# Power_Management.net
KiCad netlist of a schematic drawn in Altium Designer
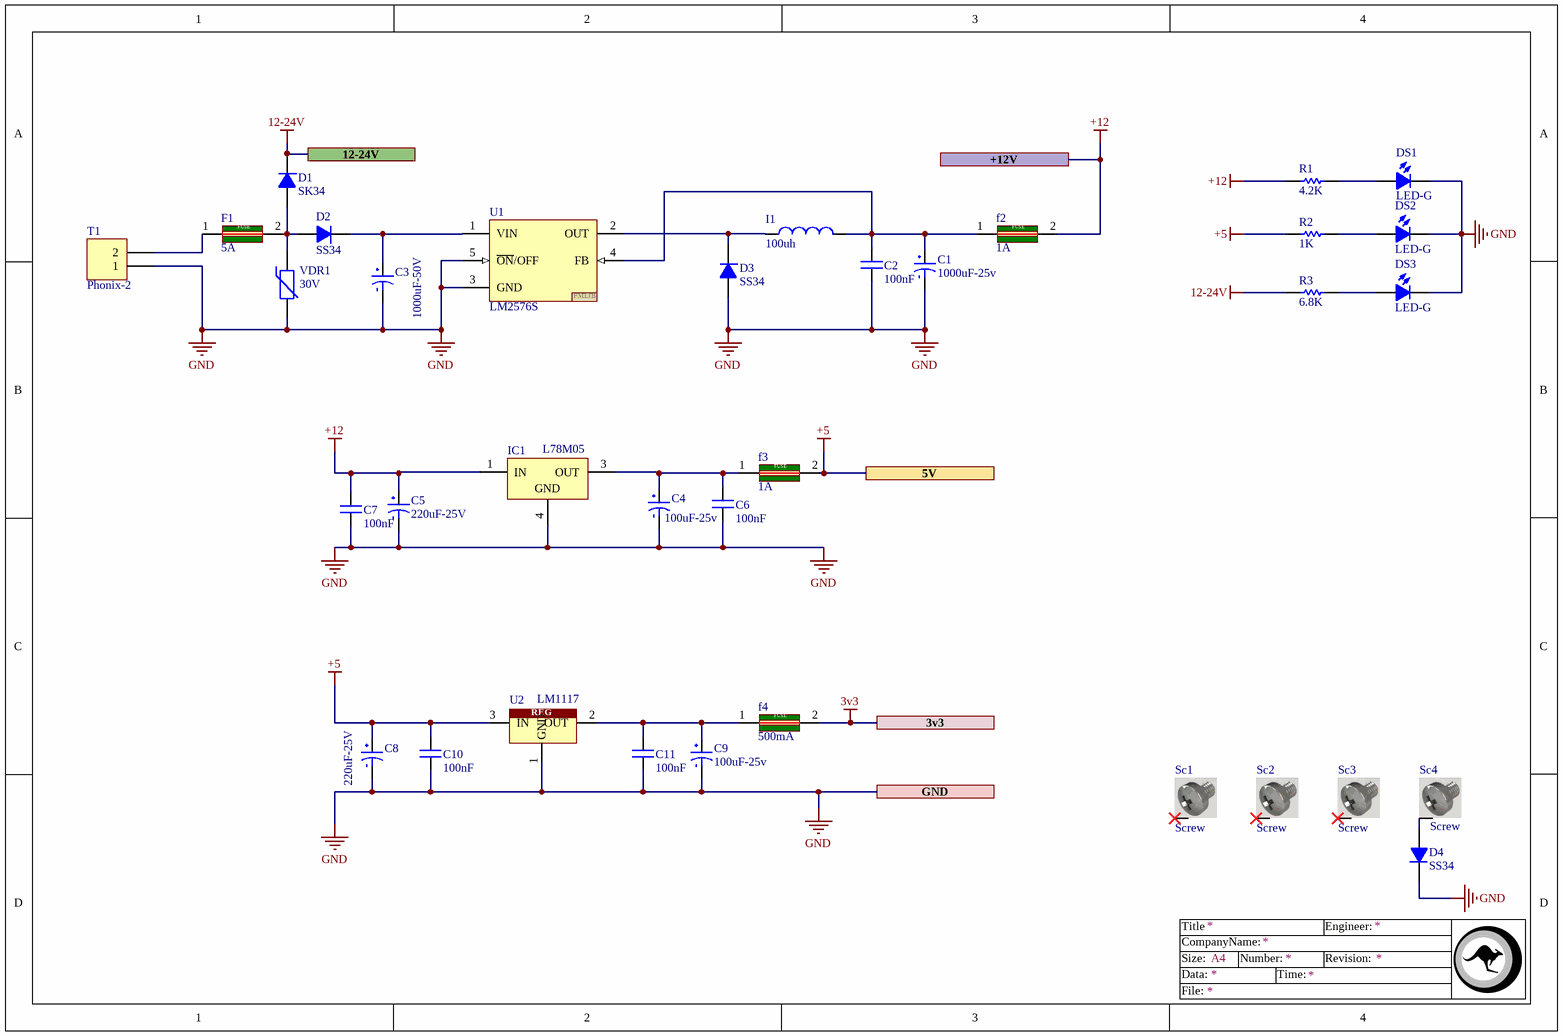
[diagram p0: Power Management.SchDoc]

(export (version "E")
  (design (tool "Eeschema 10.0.6"))
  (components
    (comp (ref "C1")
      (value "1000uF-25v")
      (footprint "Cap_4mm")
      (description "Polarity")
      (libsource (lib "PMLIB2020-V3") (part "Cap_P"))
    )
    (comp (ref "C2")
      (value "100nF")
      (footprint "CAP1206")
      (description "Surface mount Capacitor")
      (libsource (lib "PMLIB2020-V3") (part "Cap"))
    )
    (comp (ref "C3")
      (value "1000uF-50V")
      (footprint "Cap_5mm")
      (description "Polarity")
      (libsource (lib "PMLIB2020-V3") (part "Cap_P"))
    )
    (comp (ref "C4")
      (value "100uF-25v")
      (footprint "Cap_4mm")
      (description "Polarity")
      (libsource (lib "PMLIB2020-V3") (part "Cap_P"))
    )
    (comp (ref "C5")
      (value "220uF-25V")
      (footprint "Cap_4mm")
      (description "Polarity")
      (libsource (lib "PMLIB2020-V3") (part "Cap_P"))
    )
    (comp (ref "C6")
      (value "100nF")
      (footprint "Cap0805")
      (description "Surface mount Capacitor")
      (libsource (lib "PMLIB2020-V3") (part "Cap"))
    )
    (comp (ref "C7")
      (value "100nF")
      (footprint "Cap0805")
      (description "Surface mount Capacitor")
      (libsource (lib "PMLIB2020-V3") (part "Cap"))
    )
    (comp (ref "C8")
      (value "220uF-25V")
      (footprint "CAPMOL_B")
      (description "Polarity")
      (libsource (lib "PMLIB2020-V3") (part "Cap_P"))
    )
    (comp (ref "C9")
      (value "100uF-25v")
      (footprint "CAPMOL_B")
      (description "Polarity")
      (libsource (lib "PMLIB2020-V3") (part "Cap_P"))
    )
    (comp (ref "C10")
      (value "100nF")
      (footprint "Cap0805")
      (description "Surface mount Capacitor")
      (libsource (lib "PMLIB2020-V3") (part "Cap"))
    )
    (comp (ref "C11")
      (value "100nF")
      (footprint "Cap0805")
      (description "Surface mount Capacitor")
      (libsource (lib "PMLIB2020-V3") (part "Cap"))
    )
    (comp (ref "D1")
      (value "SK34")
      (footprint "Diod-3A-SMD")
      (description "Diode")
      (libsource (lib "PMLIB2020-V3") (part "Diode"))
    )
    (comp (ref "D2")
      (value "SS34")
      (footprint "Diod-1A-SMD")
      (description "Diode")
      (libsource (lib "PMLIB2020-V3") (part "Diode"))
    )
    (comp (ref "D3")
      (value "SS34")
      (footprint "Diod-1A-SMD")
      (description "Diode")
      (libsource (lib "PMLIB2020-V3") (part "Diode"))
    )
    (comp (ref "D4")
      (value "SS34")
      (footprint "Diod-1A-SMD")
      (description "Diode")
      (libsource (lib "PMLIB2020-V3") (part "Diode"))
    )
    (comp (ref "DS1")
      (value "LED-G")
      (footprint "Led0805")
      (description "LED")
      (libsource (lib "PMLIB2020-V3") (part "LED"))
    )
    (comp (ref "DS2")
      (value "LED-G")
      (footprint "Led0805")
      (description "LED")
      (libsource (lib "PMLIB2020-V3") (part "LED"))
    )
    (comp (ref "DS3")
      (value "LED-G")
      (footprint "Led0805")
      (description "LED")
      (libsource (lib "PMLIB2020-V3") (part "LED"))
    )
    (comp (ref "F1")
      (value "5A")
      (footprint "Fuse SMD")
      (description "Fuse")
      (libsource (lib "PMLIB2020-V3") (part "Fuse"))
    )
    (comp (ref "f2")
      (value "1A")
      (footprint "1206")
      (description "Fuse")
      (libsource (lib "PMLIB2020-V3") (part "Fuse"))
    )
    (comp (ref "f3")
      (value "1A")
      (footprint "1206")
      (description "Fuse")
      (libsource (lib "PMLIB2020-V3") (part "Fuse"))
    )
    (comp (ref "f4")
      (value "500mA")
      (footprint "1206")
      (description "Fuse")
      (libsource (lib "PMLIB2020-V3") (part "Fuse"))
    )
    (comp (ref "I1")
      (value "100uh")
      (footprint "INDUCTORSquare")
      (description "Indicator")
      (libsource (lib "PMLIB2020-V3") (part "Inductor"))
    )
    (comp (ref "IC1")
      (value "L78M05")
      (footprint "TO-252")
      (description "Precision 500mA Regulator")
      (libsource (lib "PMLIB2020-V3") (part "L78M05"))
    )
    (comp (ref "R1")
      (value "4.2K")
      (footprint "R0805")
      (description "Resistor")
      (libsource (lib "PMLIB2020-V3") (part "Resistor"))
    )
    (comp (ref "R2")
      (value "1K")
      (footprint "R0805")
      (description "Resistor")
      (libsource (lib "PMLIB2020-V3") (part "Resistor"))
    )
    (comp (ref "R3")
      (value "6.8K")
      (footprint "R0805")
      (description "Resistor")
      (libsource (lib "PMLIB2020-V3") (part "Resistor"))
    )
    (comp (ref "Sc1")
      (value "Screw")
      (footprint "Screw")
      (description "Screw 3mm")
      (libsource (lib "PMLIB2020-V3") (part "Screw"))
    )
    (comp (ref "Sc2")
      (value "Screw")
      (footprint "Screw")
      (description "Screw 3mm")
      (libsource (lib "PMLIB2020-V3") (part "Screw"))
    )
    (comp (ref "Sc3")
      (value "Screw")
      (footprint "Screw")
      (description "Screw 3mm")
      (libsource (lib "PMLIB2020-V3") (part "Screw"))
    )
    (comp (ref "Sc4")
      (value "Screw")
      (footprint "Screw")
      (description "Screw 3mm")
      (libsource (lib "PMLIB2020-V3") (part "Screw"))
    )
    (comp (ref "T1")
      (value "Phonix-2")
      (footprint "Phonix-2")
      (description "Connector")
      (libsource (lib "PMLIB2020-V3") (part "Phonix-2"))
    )
    (comp (ref "U1")
      (value "LM2576S")
      (footprint "LM2576S")
      (description "Regulator")
      (libsource (lib "PMLIB2020-V3") (part "LM2576S"))
    )
    (comp (ref "U2")
      (value "LM1117")
      (footprint "DPACK")
      (description "Regulator")
      (libsource (lib "PMLIB2020-V3") (part "LM1117"))
    )
    (comp (ref "VDR1")
      (value "30V")
      (footprint "Varistor")
      (libsource (lib "PMLIB2020-V3") (part "Varistor"))
    )
  )
  (nets
    (net (code "1") (name "+5") (class "Default")
      (node (ref "C10") (pin "2") (pinfunction "2_2") (pintype "passive"))
      (node (ref "C8") (pin "2") (pinfunction "2_2") (pintype "passive"))
      (node (ref "R2") (pin "2") (pinfunction "2_2") (pintype "passive"))
      (node (ref "U2") (pin "3") (pinfunction "IN_3") (pintype "passive"))
      (node (ref "f3") (pin "2") (pinfunction "OUT_2") (pintype "passive"))
    )
    (net (code "2") (name "+12") (class "Default")
      (node (ref "C5") (pin "2") (pinfunction "2_2") (pintype "passive"))
      (node (ref "C7") (pin "2") (pinfunction "2_2") (pintype "passive"))
      (node (ref "IC1") (pin "1") (pinfunction "IN_1") (pintype "power_in"))
      (node (ref "R1") (pin "2") (pinfunction "2_2") (pintype "passive"))
      (node (ref "f2") (pin "2") (pinfunction "OUT_2") (pintype "passive"))
    )
    (net (code "3") (name "3v3") (class "Default")
      (node (ref "f4") (pin "2") (pinfunction "OUT_2") (pintype "passive"))
    )
    (net (code "4") (name "12-24V") (class "Default")
      (node (ref "D1") (pin "K") (pinfunction "K_K") (pintype "passive"))
      (node (ref "R3") (pin "2") (pinfunction "2_2") (pintype "passive"))
    )
    (net (code "5") (name "GND") (class "Default")
      (node (ref "C1") (pin "1") (pinfunction "1_1") (pintype "passive"))
      (node (ref "C10") (pin "1") (pinfunction "1_1") (pintype "passive"))
      (node (ref "C11") (pin "1") (pinfunction "1_1") (pintype "passive"))
      (node (ref "C2") (pin "1") (pinfunction "1_1") (pintype "passive"))
      (node (ref "C3") (pin "1") (pinfunction "1_1") (pintype "passive"))
      (node (ref "C4") (pin "1") (pinfunction "1_1") (pintype "passive"))
      (node (ref "C5") (pin "1") (pinfunction "1_1") (pintype "passive"))
      (node (ref "C6") (pin "1") (pinfunction "1_1") (pintype "passive"))
      (node (ref "C7") (pin "1") (pinfunction "1_1") (pintype "passive"))
      (node (ref "C8") (pin "1") (pinfunction "1_1") (pintype "passive"))
      (node (ref "C9") (pin "1") (pinfunction "1_1") (pintype "passive"))
      (node (ref "D3") (pin "A") (pinfunction "A_A") (pintype "passive"))
      (node (ref "D4") (pin "K") (pinfunction "K_K") (pintype "passive"))
      (node (ref "DS1") (pin "K") (pinfunction "K_K") (pintype "passive"))
      (node (ref "DS2") (pin "K") (pinfunction "K_K") (pintype "passive"))
      (node (ref "DS3") (pin "K") (pinfunction "K_K") (pintype "passive"))
      (node (ref "IC1") (pin "4") (pinfunction "GND_4") (pintype "power_in"))
      (node (ref "T1") (pin "1") (pinfunction "1_1") (pintype "passive"))
      (node (ref "U1") (pin "3") (pinfunction "GND_3") (pintype "power_in"))
      (node (ref "U1") (pin "5") (pinfunction "~{ON}/OFF_5") (pintype "input"))
      (node (ref "U2") (pin "1") (pinfunction "GND_1") (pintype "passive"))
      (node (ref "VDR1") (pin "1") (pinfunction "1_1") (pintype "passive"))
    )
    (net (code "6") (name "Net-(D4-PadA)") (class "Default")
      (node (ref "D4") (pin "A") (pinfunction "A_A") (pintype "passive"))
      (node (ref "Sc4") (pin "S") (pinfunction "S_S") (pintype "passive"))
    )
    (net (code "7") (name "Net-(DS1-PadA)") (class "Default")
      (node (ref "DS1") (pin "A") (pinfunction "A_A") (pintype "passive"))
      (node (ref "R1") (pin "1") (pinfunction "1_1") (pintype "passive"))
    )
    (net (code "8") (name "Net-(DS2-PadA)") (class "Default")
      (node (ref "DS2") (pin "A") (pinfunction "A_A") (pintype "passive"))
      (node (ref "R2") (pin "1") (pinfunction "1_1") (pintype "passive"))
    )
    (net (code "9") (name "Net-(DS3-PadA)") (class "Default")
      (node (ref "DS3") (pin "A") (pinfunction "A_A") (pintype "passive"))
      (node (ref "R3") (pin "1") (pinfunction "1_1") (pintype "passive"))
    )
    (net (code "10") (name "Net-(F1-IN)") (class "Default")
      (node (ref "F1") (pin "1") (pinfunction "IN_1") (pintype "passive"))
      (node (ref "T1") (pin "2") (pinfunction "2_2") (pintype "passive"))
    )
    (net (code "11") (name "Net-(F1-OUT)") (class "Default")
      (node (ref "D1") (pin "A") (pinfunction "A_A") (pintype "passive"))
      (node (ref "D2") (pin "A") (pinfunction "A_A") (pintype "passive"))
      (node (ref "F1") (pin "2") (pinfunction "OUT_2") (pintype "passive"))
      (node (ref "VDR1") (pin "2") (pinfunction "2_2") (pintype "passive"))
    )
    (net (code "12") (name "Net-(IC1-OUT)") (class "Default")
      (node (ref "C4") (pin "2") (pinfunction "2_2") (pintype "passive"))
      (node (ref "C6") (pin "2") (pinfunction "2_2") (pintype "passive"))
      (node (ref "IC1") (pin "3") (pinfunction "OUT_3") (pintype "power_in"))
      (node (ref "f3") (pin "1") (pinfunction "IN_1") (pintype "passive"))
    )
    (net (code "13") (name "Net-(U1-FB)") (class "Default")
      (node (ref "C1") (pin "2") (pinfunction "2_2") (pintype "passive"))
      (node (ref "C2") (pin "2") (pinfunction "2_2") (pintype "passive"))
      (node (ref "I1") (pin "2") (pinfunction "2_2") (pintype "passive"))
      (node (ref "U1") (pin "4") (pinfunction "FB_4") (pintype "input"))
      (node (ref "f2") (pin "1") (pinfunction "IN_1") (pintype "passive"))
    )
    (net (code "14") (name "Net-(U1-OUT)") (class "Default")
      (node (ref "D3") (pin "K") (pinfunction "K_K") (pintype "passive"))
      (node (ref "I1") (pin "1") (pinfunction "1_1") (pintype "passive"))
      (node (ref "U1") (pin "2") (pinfunction "OUT_2") (pintype "power_in"))
    )
    (net (code "15") (name "Net-(U1-VIN)") (class "Default")
      (node (ref "C3") (pin "2") (pinfunction "2_2") (pintype "passive"))
      (node (ref "D2") (pin "K") (pinfunction "K_K") (pintype "passive"))
      (node (ref "U1") (pin "1") (pinfunction "VIN_1") (pintype "power_in"))
    )
    (net (code "16") (name "Net-(U2-OUT)") (class "Default")
      (node (ref "C11") (pin "2") (pinfunction "2_2") (pintype "passive"))
      (node (ref "C9") (pin "2") (pinfunction "2_2") (pintype "passive"))
      (node (ref "U2") (pin "2") (pinfunction "OUT_2") (pintype "passive"))
      (node (ref "f4") (pin "1") (pinfunction "IN_1") (pintype "passive"))
    )
    (net (code "17") (name "unconnected-(Sc1-PadS)") (class "Default")
      (node (ref "Sc1") (pin "S") (pinfunction "S_S") (pintype "passive+no_connect"))
    )
    (net (code "18") (name "unconnected-(Sc2-PadS)") (class "Default")
      (node (ref "Sc2") (pin "S") (pinfunction "S_S") (pintype "passive+no_connect"))
    )
    (net (code "19") (name "unconnected-(Sc3-PadS)") (class "Default")
      (node (ref "Sc3") (pin "S") (pinfunction "S_S") (pintype "passive+no_connect"))
    )
  )
)
